# dummy_load_moved.net
KiCad netlist of a schematic drawn in EAGLE
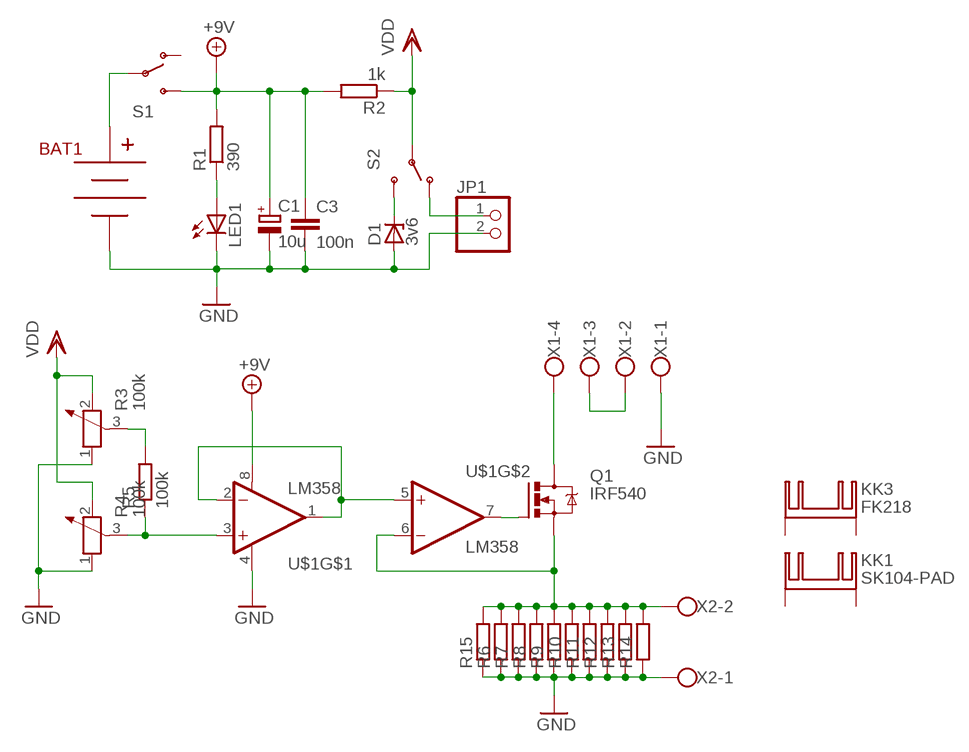
[diagram p0: schematic, sheet 1]

(export (version "E")
  (design (tool "Eeschema 10.0.6"))
  (components
    (comp (ref "BAT1")
      (value "BC9VPC")
      (footprint "eagle-import:BC9VPC")
      (libsource (lib "eagle-import") (part "BC9VPC"))
    )
    (comp (ref "C1")
      (value "10u")
      (footprint "eagle-import:TT2D5L")
      (libsource (lib "eagle-import") (part "CPOL-EUTT2D5L"))
    )
    (comp (ref "C3")
      (value "100n")
      (footprint "eagle-import:C025-025X050")
      (libsource (lib "eagle-import") (part "C-EU025-025X050"))
    )
    (comp (ref "D1")
      (value "3v6")
      (footprint "eagle-import:ZDIO-5")
      (libsource (lib "eagle-import") (part "ZENER-DIODEZD-5"))
    )
    (comp (ref "JP1")
      (value "PINHD-1X2")
      (footprint "eagle-import:1X02")
      (libsource (lib "eagle-import") (part "PINHD-1X2"))
    )
    (comp (ref "KK1")
      (value "SK104-PAD")
      (footprint "eagle-import:SK104-PAD")
      (libsource (lib "eagle-import") (part "SK104-PAD"))
    )
    (comp (ref "KK3")
      (value "FK218")
      (footprint "eagle-import:FK218")
      (libsource (lib "eagle-import") (part "FK218"))
    )
    (comp (ref "LED1")
      (value "LED5MM")
      (footprint "eagle-import:LED5MM")
      (libsource (lib "eagle-import") (part "LED5MM"))
    )
    (comp (ref "Q1")
      (value "IRF540")
      (footprint "eagle-import:TO220BV")
      (libsource (lib "eagle-import") (part "IRF540"))
    )
    (comp (ref "R1")
      (value "390")
      (footprint "eagle-import:0204_7")
      (libsource (lib "eagle-import") (part "R-EU_0204/7"))
    )
    (comp (ref "R2")
      (value "1k")
      (footprint "eagle-import:0204_7")
      (libsource (lib "eagle-import") (part "R-EU_0204/7"))
    )
    (comp (ref "R3")
      (value "100k")
      (footprint "eagle-import:PT-10")
      (libsource (lib "eagle-import") (part "POTENTIOMETER_PT-10"))
    )
    (comp (ref "R4")
      (value "100k")
      (footprint "eagle-import:PT-10")
      (libsource (lib "eagle-import") (part "POTENTIOMETER_PT-10"))
    )
    (comp (ref "R5")
      (value "100k")
      (footprint "eagle-import:0204_7")
      (libsource (lib "eagle-import") (part "R-EU_0204/7"))
    )
    (comp (ref "R6")
      (value "R-EU_0207/7")
      (footprint "eagle-import:0207_7")
      (libsource (lib "eagle-import") (part "R-EU_0207/7"))
    )
    (comp (ref "R7")
      (value "R-EU_0207/7")
      (footprint "eagle-import:0207_7")
      (libsource (lib "eagle-import") (part "R-EU_0207/7"))
    )
    (comp (ref "R8")
      (value "R-EU_0207/7")
      (footprint "eagle-import:0207_7")
      (libsource (lib "eagle-import") (part "R-EU_0207/7"))
    )
    (comp (ref "R9")
      (value "R-EU_0207/7")
      (footprint "eagle-import:0207_7")
      (libsource (lib "eagle-import") (part "R-EU_0207/7"))
    )
    (comp (ref "R10")
      (value "R-EU_0207/7")
      (footprint "eagle-import:0207_7")
      (libsource (lib "eagle-import") (part "R-EU_0207/7"))
    )
    (comp (ref "R11")
      (value "R-EU_0207/7")
      (footprint "eagle-import:0207_7")
      (libsource (lib "eagle-import") (part "R-EU_0207/7"))
    )
    (comp (ref "R12")
      (value "R-EU_0207/7")
      (footprint "eagle-import:0207_7")
      (libsource (lib "eagle-import") (part "R-EU_0207/7"))
    )
    (comp (ref "R13")
      (value "R-EU_0207/7")
      (footprint "eagle-import:0207_7")
      (libsource (lib "eagle-import") (part "R-EU_0207/7"))
    )
    (comp (ref "R14")
      (value "R-EU_0207/7")
      (footprint "eagle-import:0207_7")
      (libsource (lib "eagle-import") (part "R-EU_0207/7"))
    )
    (comp (ref "R15")
      (value "R-EU_0207/7")
      (footprint "eagle-import:0207_7")
      (libsource (lib "eagle-import") (part "R-EU_0207/7"))
    )
    (comp (ref "S1")
      (value "SWITCH-SPSTPTH")
      (footprint "eagle-import:SWITCH-SPDT")
      (libsource (lib "eagle-import") (part "SWITCH-SPSTPTH"))
    )
    (comp (ref "S2")
      (value "SWITCH-SPSTPTH")
      (footprint "eagle-import:SWITCH-SPDT")
      (libsource (lib "eagle-import") (part "SWITCH-SPSTPTH"))
    )
    (comp (ref "U$1")
      (value "LM358")
      (footprint "eagle-import:DIP08")
      (libsource (lib "eagle-import") (part "LM358"))
    )
    (comp (ref "X1")
      (value "W237-4")
      (footprint "eagle-import:W237-4")
      (libsource (lib "eagle-import") (part "W237-4"))
    )
    (comp (ref "X2")
      (value "W237-102")
      (footprint "eagle-import:W237-102")
      (fields (field (name "MPN") "237-102"))
      (libsource (lib "eagle-import") (part "W237-102"))
    )
  )
  (nets
    (net (code "1") (name "+9V") (class "Default")
      (node (ref "C1") (pin "+") (pinfunction "+_+") (pintype "passive"))
      (node (ref "C3") (pin "1") (pinfunction "1_1") (pintype "passive"))
      (node (ref "R1") (pin "2") (pinfunction "2_2") (pintype "passive"))
      (node (ref "R2") (pin "2") (pinfunction "2_2") (pintype "passive"))
      (node (ref "S1") (pin "3") (pinfunction "S_3") (pintype "passive"))
      (node (ref "U$1") (pin "8") (pinfunction "V+_8") (pintype "power_in"))
    )
    (net (code "2") (name "GND") (class "Default")
      (node (ref "BAT1") (pin "V-") (pinfunction "V-_V-") (pintype "bidirectional"))
      (node (ref "C1") (pin "-") (pinfunction "-_-") (pintype "passive"))
      (node (ref "C3") (pin "2") (pinfunction "2_2") (pintype "passive"))
      (node (ref "D1") (pin "A") (pinfunction "A_A") (pintype "passive"))
      (node (ref "JP1") (pin "2") (pinfunction "2_2") (pintype "passive"))
      (node (ref "LED1") (pin "K") (pinfunction "C_K") (pintype "passive"))
      (node (ref "R10") (pin "1") (pinfunction "1_1") (pintype "passive"))
      (node (ref "R11") (pin "1") (pinfunction "1_1") (pintype "passive"))
      (node (ref "R12") (pin "1") (pinfunction "1_1") (pintype "passive"))
      (node (ref "R13") (pin "1") (pinfunction "1_1") (pintype "passive"))
      (node (ref "R14") (pin "1") (pinfunction "1_1") (pintype "passive"))
      (node (ref "R15") (pin "1") (pinfunction "1_1") (pintype "passive"))
      (node (ref "R3") (pin "1") (pinfunction "1_1") (pintype "passive"))
      (node (ref "R4") (pin "1") (pinfunction "1_1") (pintype "passive"))
      (node (ref "R6") (pin "1") (pinfunction "1_1") (pintype "passive"))
      (node (ref "R7") (pin "1") (pinfunction "1_1") (pintype "passive"))
      (node (ref "R8") (pin "1") (pinfunction "1_1") (pintype "passive"))
      (node (ref "R9") (pin "1") (pinfunction "1_1") (pintype "passive"))
      (node (ref "U$1") (pin "4") (pinfunction "V-_4") (pintype "power_in"))
      (node (ref "X1") (pin "1") (pinfunction "KL_1") (pintype "passive"))
      (node (ref "X2") (pin "1") (pinfunction "KL_1") (pintype "passive"))
    )
    (net (code "3") (name "Net-(LED1-PadA)") (class "Default")
      (node (ref "LED1") (pin "A") (pinfunction "A_A") (pintype "passive"))
      (node (ref "R1") (pin "1") (pinfunction "1_1") (pintype "passive"))
    )
    (net (code "4") (name "Net-(R3-Pad3)") (class "Default")
      (node (ref "R3") (pin "3") (pinfunction "3_3") (pintype "passive"))
      (node (ref "R5") (pin "2") (pinfunction "2_2") (pintype "passive"))
    )
    (net (code "5") (name "Net-(S1-P)") (class "Default")
      (node (ref "BAT1") (pin "V+") (pinfunction "V+_V+") (pintype "bidirectional"))
      (node (ref "S1") (pin "2") (pinfunction "P_2") (pintype "passive"))
    )
    (net (code "6") (name "Net-(S2-O)") (class "Default")
      (node (ref "JP1") (pin "1") (pinfunction "1_1") (pintype "passive"))
      (node (ref "S2") (pin "1") (pinfunction "O_1") (pintype "passive"))
    )
    (net (code "7") (name "Net-(S2-S)") (class "Default")
      (node (ref "D1") (pin "C") (pinfunction "C_C") (pintype "passive"))
      (node (ref "S2") (pin "3") (pinfunction "S_3") (pintype "passive"))
    )
    (net (code "8") (name "Net-(U$1A-+IN)") (class "Default")
      (node (ref "R4") (pin "3") (pinfunction "3_3") (pintype "passive"))
      (node (ref "R5") (pin "1") (pinfunction "1_1") (pintype "passive"))
      (node (ref "U$1") (pin "3") (pinfunction "+IN_3") (pintype "input"))
    )
    (net (code "9") (name "Net-(U$1A--IN)") (class "Default")
      (node (ref "U$1") (pin "1") (pinfunction "OUT_1") (pintype "output"))
      (node (ref "U$1") (pin "2") (pinfunction "-IN_2") (pintype "input"))
      (node (ref "U$1") (pin "5") (pinfunction "+IN_5") (pintype "input"))
    )
    (net (code "10") (name "Net-(U$1B--IN)") (class "Default")
      (node (ref "Q1") (pin "S") (pinfunction "S_S") (pintype "passive"))
      (node (ref "R10") (pin "2") (pinfunction "2_2") (pintype "passive"))
      (node (ref "R11") (pin "2") (pinfunction "2_2") (pintype "passive"))
      (node (ref "R12") (pin "2") (pinfunction "2_2") (pintype "passive"))
      (node (ref "R13") (pin "2") (pinfunction "2_2") (pintype "passive"))
      (node (ref "R14") (pin "2") (pinfunction "2_2") (pintype "passive"))
      (node (ref "R15") (pin "2") (pinfunction "2_2") (pintype "passive"))
      (node (ref "R6") (pin "2") (pinfunction "2_2") (pintype "passive"))
      (node (ref "R7") (pin "2") (pinfunction "2_2") (pintype "passive"))
      (node (ref "R8") (pin "2") (pinfunction "2_2") (pintype "passive"))
      (node (ref "R9") (pin "2") (pinfunction "2_2") (pintype "passive"))
      (node (ref "U$1") (pin "6") (pinfunction "-IN_6") (pintype "input"))
      (node (ref "X2") (pin "2") (pinfunction "KL_2") (pintype "passive"))
    )
    (net (code "11") (name "Net-(U$1B-OUT)") (class "Default")
      (node (ref "Q1") (pin "G") (pinfunction "G_G") (pintype "passive"))
      (node (ref "U$1") (pin "7") (pinfunction "OUT_7") (pintype "output"))
    )
    (net (code "12") (name "Net-(X1B-KL)") (class "Default")
      (node (ref "X1") (pin "2") (pinfunction "KL_2") (pintype "passive"))
      (node (ref "X1") (pin "3") (pinfunction "KL_3") (pintype "passive"))
    )
    (net (code "13") (name "Net-(X1D-KL)") (class "Default")
      (node (ref "Q1") (pin "D") (pinfunction "D_D") (pintype "passive"))
      (node (ref "X1") (pin "4") (pinfunction "KL_4") (pintype "passive"))
    )
    (net (code "14") (name "VDD") (class "Default")
      (node (ref "R2") (pin "1") (pinfunction "1_1") (pintype "passive"))
      (node (ref "R3") (pin "2") (pinfunction "2_2") (pintype "passive"))
      (node (ref "R4") (pin "2") (pinfunction "2_2") (pintype "passive"))
      (node (ref "S2") (pin "2") (pinfunction "P_2") (pintype "passive"))
    )
    (net (code "15") (name "unconnected-(KK1-K-PadK1)") (class "Default")
      (node (ref "KK1") (pin "K1") (pinfunction "K_K1") (pintype "passive"))
    )
    (net (code "16") (name "unconnected-(KK1-K-PadK2)") (class "Default")
      (node (ref "KK1") (pin "K2") (pinfunction "K_K2") (pintype "passive"))
    )
    (net (code "17") (name "unconnected-(KK3-K-PadA2,2)") (class "Default")
      (node (ref "KK3") (pin "A2,2") (pinfunction "K_A2,2") (pintype "passive"))
    )
    (net (code "18") (name "unconnected-(KK3-K-PadB2,2)") (class "Default")
      (node (ref "KK3") (pin "B2,2") (pinfunction "K_B2,2") (pintype "passive"))
    )
    (net (code "19") (name "unconnected-(S1-O-Pad1)") (class "Default")
      (node (ref "S1") (pin "1") (pinfunction "O_1") (pintype "passive"))
    )
  )
)
